# tick-ref-gps.net
KiCad netlist of a schematic drawn in EAGLE
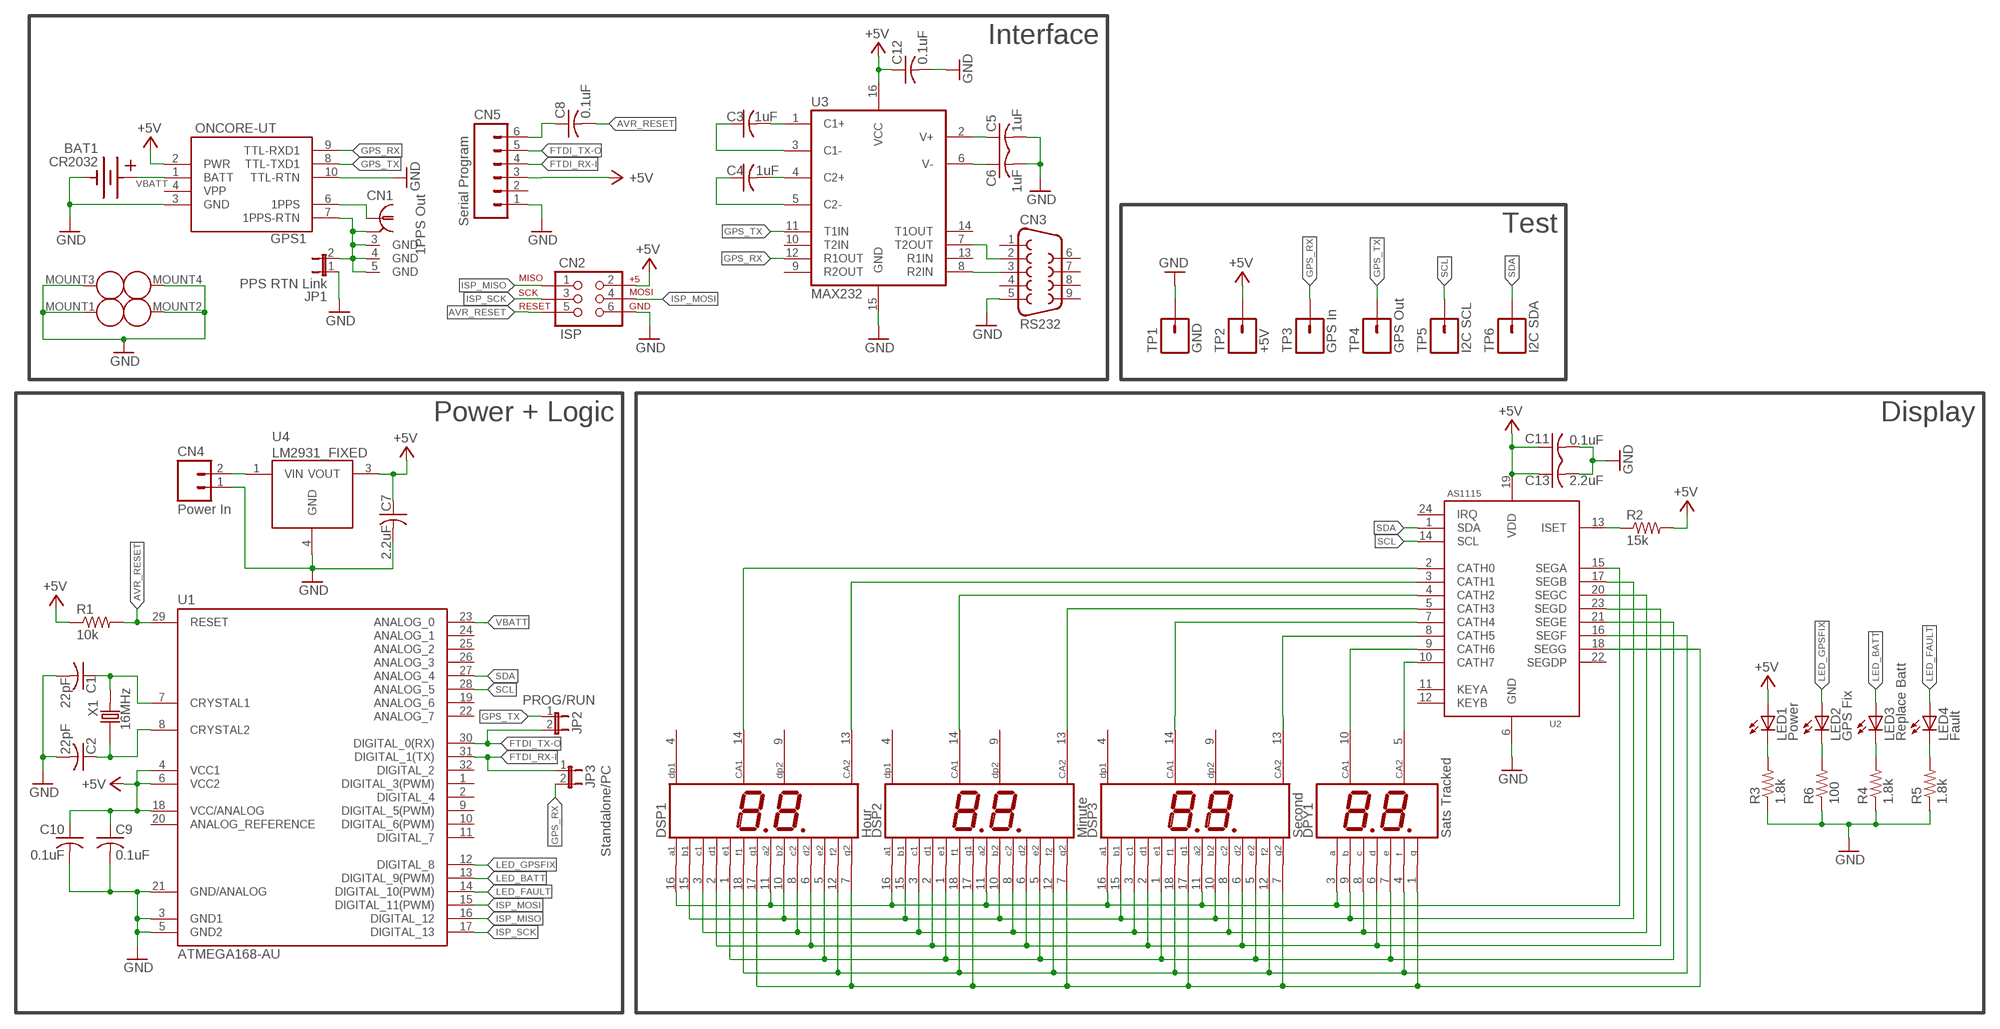
[diagram p0: schematic, sheet 1]

(export (version "E")
  (design (tool "Eeschema 10.0.6"))
  (components
    (comp (ref "BAT1")
      (value "CR2032")
      (footprint "eagle-import:BK-912-CR2032")
      (libsource (lib "eagle-import") (part "CR2032"))
    )
    (comp (ref "C1")
      (value "22pF")
      (footprint "eagle-import:C0603")
      (libsource (lib "eagle-import") (part "C-USC0603"))
    )
    (comp (ref "C2")
      (value "22pF")
      (footprint "eagle-import:C0603")
      (libsource (lib "eagle-import") (part "C-USC0603"))
    )
    (comp (ref "C3")
      (value "1uF")
      (footprint "eagle-import:C0603")
      (libsource (lib "eagle-import") (part "C-USC0603"))
    )
    (comp (ref "C4")
      (value "1uF")
      (footprint "eagle-import:C0603")
      (libsource (lib "eagle-import") (part "C-USC0603"))
    )
    (comp (ref "C5")
      (value "1uF")
      (footprint "eagle-import:C0603")
      (libsource (lib "eagle-import") (part "C-USC0603"))
    )
    (comp (ref "C6")
      (value "1uF")
      (footprint "eagle-import:C0603")
      (libsource (lib "eagle-import") (part "C-USC0603"))
    )
    (comp (ref "C7")
      (value "2.2uF")
      (footprint "eagle-import:C0805")
      (libsource (lib "eagle-import") (part "C-USC0805"))
    )
    (comp (ref "C8")
      (value "0.1uF")
      (footprint "eagle-import:C0603")
      (libsource (lib "eagle-import") (part "C-USC0603"))
    )
    (comp (ref "C9")
      (value "0.1uF")
      (footprint "eagle-import:C0603")
      (libsource (lib "eagle-import") (part "C-USC0603"))
    )
    (comp (ref "C10")
      (value "0.1uF")
      (footprint "eagle-import:C0603")
      (libsource (lib "eagle-import") (part "C-USC0603"))
    )
    (comp (ref "C11")
      (value "0.1uF")
      (footprint "eagle-import:C0603")
      (libsource (lib "eagle-import") (part "C-USC0603"))
    )
    (comp (ref "C12")
      (value "0.1uF")
      (footprint "eagle-import:C0603")
      (libsource (lib "eagle-import") (part "C-USC0603"))
    )
    (comp (ref "C13")
      (value "2.2uF")
      (footprint "eagle-import:C0805")
      (libsource (lib "eagle-import") (part "C-USC0805"))
    )
    (comp (ref "CN1")
      (value "1PPS Out")
      (footprint "eagle-import:B35N57")
      (libsource (lib "eagle-import") (part "B35N57"))
    )
    (comp (ref "CN2")
      (value "ISP")
      (footprint "eagle-import:2X3_LOCK")
      (libsource (lib "eagle-import") (part "AVR_SPI_PRG_62X3_LOCK"))
    )
    (comp (ref "CN3")
      (value "RS232")
      (footprint "eagle-import:F09VP")
      (libsource (lib "eagle-import") (part "F09VP"))
    )
    (comp (ref "CN4")
      (value "Power In")
      (footprint "eagle-import:MOLEX-1X2_LOCK")
      (libsource (lib "eagle-import") (part "M02POLAR_LOCK"))
    )
    (comp (ref "CN5")
      (value "Serial Program")
      (footprint "eagle-import:1X06_LOCK")
      (libsource (lib "eagle-import") (part "M06LOCK"))
    )
    (comp (ref "DPY1")
      (value "Sats Tracked")
      (footprint "eagle-import:LDD-F302NI")
      (libsource (lib "eagle-import") (part "LUMEX-LDD-F302NI"))
    )
    (comp (ref "DSP1")
      (value "Hour")
      (footprint "eagle-import:HDSP-R")
      (libsource (lib "eagle-import") (part "HD-K121"))
    )
    (comp (ref "DSP2")
      (value "Minute")
      (footprint "eagle-import:HDSP-R")
      (libsource (lib "eagle-import") (part "HD-K121"))
    )
    (comp (ref "DSP3")
      (value "Second")
      (footprint "eagle-import:HDSP-R")
      (libsource (lib "eagle-import") (part "HD-K121"))
    )
    (comp (ref "GPS1")
      (value "ONCORE-UT")
      (footprint "eagle-import:ONCORE-UT")
      (libsource (lib "eagle-import") (part "ONCORE-UT"))
    )
    (comp (ref "JP1")
      (value "PPS RTN Link")
      (footprint "eagle-import:SJ_2S-NO")
      (libsource (lib "eagle-import") (part "JUMPER-2SMD-NO"))
    )
    (comp (ref "JP2")
      (value "PROG/RUN")
      (footprint "eagle-import:1X02_LOCK")
      (libsource (lib "eagle-import") (part "JUMPER-2PTH_LOCK"))
    )
    (comp (ref "JP3")
      (value "Standalone/PC")
      (footprint "eagle-import:SJ_2S-NO")
      (libsource (lib "eagle-import") (part "JUMPER-2SMD-NO"))
    )
    (comp (ref "LED1")
      (value "Power")
      (footprint "eagle-import:LED5MM")
      (libsource (lib "eagle-import") (part "LED5MM"))
    )
    (comp (ref "LED2")
      (value "GPS Fix")
      (footprint "eagle-import:LED5MM")
      (libsource (lib "eagle-import") (part "LED5MM"))
    )
    (comp (ref "LED3")
      (value "Replace Batt")
      (footprint "eagle-import:LED5MM")
      (libsource (lib "eagle-import") (part "LED5MM"))
    )
    (comp (ref "LED4")
      (value "Fault")
      (footprint "eagle-import:LED5MM")
      (libsource (lib "eagle-import") (part "LED5MM"))
    )
    (comp (ref "R1")
      (value "10k")
      (footprint "eagle-import:R0603")
      (libsource (lib "eagle-import") (part "R-US_R0603"))
    )
    (comp (ref "R2")
      (value "15k")
      (footprint "eagle-import:R0603")
      (libsource (lib "eagle-import") (part "R-US_R0603"))
    )
    (comp (ref "R3")
      (value "1.8k")
      (footprint "eagle-import:R0603")
      (libsource (lib "eagle-import") (part "R-US_R0603"))
    )
    (comp (ref "R4")
      (value "1.8k")
      (footprint "eagle-import:R0603")
      (libsource (lib "eagle-import") (part "R-US_R0603"))
    )
    (comp (ref "R5")
      (value "1.8k")
      (footprint "eagle-import:R0603")
      (libsource (lib "eagle-import") (part "R-US_R0603"))
    )
    (comp (ref "R6")
      (value "100")
      (footprint "eagle-import:R0603")
      (libsource (lib "eagle-import") (part "R-US_R0603"))
    )
    (comp (ref "TP1")
      (value "GND")
      (footprint "eagle-import:1X01")
      (libsource (lib "eagle-import") (part "M01PTH"))
    )
    (comp (ref "TP2")
      (value "+5V")
      (footprint "eagle-import:1X01")
      (libsource (lib "eagle-import") (part "M01PTH"))
    )
    (comp (ref "TP3")
      (value "GPS In")
      (footprint "eagle-import:1X01")
      (libsource (lib "eagle-import") (part "M01PTH"))
    )
    (comp (ref "TP4")
      (value "GPS Out")
      (footprint "eagle-import:1X01")
      (libsource (lib "eagle-import") (part "M01PTH"))
    )
    (comp (ref "TP5")
      (value "I2C SCL")
      (footprint "eagle-import:1X01")
      (libsource (lib "eagle-import") (part "M01PTH"))
    )
    (comp (ref "TP6")
      (value "I2C SDA")
      (footprint "eagle-import:1X01")
      (libsource (lib "eagle-import") (part "M01PTH"))
    )
    (comp (ref "U1")
      (value "ATMEGA168-AU")
      (footprint "eagle-import:TQFP32-08")
      (libsource (lib "eagle-import") (part "ATMEGA168-AU"))
    )
    (comp (ref "U2")
      (value "AS1115")
      (footprint "eagle-import:QSOP24")
      (libsource (lib "eagle-import") (part "AS1115"))
    )
    (comp (ref "U3")
      (value "MAX232")
      (footprint "eagle-import:SO016")
      (libsource (lib "eagle-import") (part "MAX232SOIC16"))
    )
    (comp (ref "U4")
      (value "LM2931_FIXED")
      (footprint "eagle-import:DPAK")
      (libsource (lib "eagle-import") (part "LM2931_FIXED"))
    )
    (comp (ref "X1")
      (value "16MHz")
      (footprint "eagle-import:NX5032GA")
      (libsource (lib "eagle-import") (part "NX5032GA"))
    )
  )
  (nets
    (net (code "1") (name "+5V") (class "Default")
      (node (ref "C10") (pin "1") (pinfunction "1_1") (pintype "passive"))
      (node (ref "C11") (pin "1") (pinfunction "1_1") (pintype "passive"))
      (node (ref "C12") (pin "1") (pinfunction "1_1") (pintype "passive"))
      (node (ref "C13") (pin "1") (pinfunction "1_1") (pintype "passive"))
      (node (ref "C7") (pin "1") (pinfunction "1_1") (pintype "passive"))
      (node (ref "C9") (pin "1") (pinfunction "1_1") (pintype "passive"))
      (node (ref "CN2") (pin "2") (pinfunction "2_2") (pintype "passive"))
      (node (ref "CN5") (pin "3") (pinfunction "3_3") (pintype "passive"))
      (node (ref "GPS1") (pin "2") (pinfunction "PWR_2") (pintype "power_in"))
      (node (ref "LED1") (pin "A") (pinfunction "A_A") (pintype "passive"))
      (node (ref "R1") (pin "1") (pinfunction "1_1") (pintype "passive"))
      (node (ref "R2") (pin "2") (pinfunction "2_2") (pintype "passive"))
      (node (ref "TP2") (pin "1") (pinfunction "1_1") (pintype "passive"))
      (node (ref "U1") (pin "18") (pinfunction "VCC/ANALOG_18") (pintype "passive"))
      (node (ref "U1") (pin "4") (pinfunction "VCC1_4") (pintype "power_in"))
      (node (ref "U1") (pin "6") (pinfunction "VCC2_6") (pintype "power_in"))
      (node (ref "U2") (pin "19") (pinfunction "VDD_19") (pintype "power_in"))
      (node (ref "U3") (pin "16") (pinfunction "VCC_16") (pintype "bidirectional"))
      (node (ref "U4") (pin "3") (pinfunction "VOUT_3") (pintype "bidirectional"))
    )
    (net (code "2") (name "/VPP") (class "Default")
      (node (ref "GPS1") (pin "4") (pinfunction "VPP_4") (pintype "power_in"))
    )
    (net (code "3") (name "AVR_RESET") (class "Default")
      (node (ref "C8") (pin "2") (pinfunction "2_2") (pintype "passive"))
      (node (ref "CN2") (pin "5") (pinfunction "5_5") (pintype "passive"))
      (node (ref "R1") (pin "2") (pinfunction "2_2") (pintype "passive"))
      (node (ref "U1") (pin "29") (pinfunction "RESET_29") (pintype "bidirectional"))
    )
    (net (code "4") (name "FTDI_RX-I") (class "Default")
      (node (ref "CN5") (pin "4") (pinfunction "4_4") (pintype "passive"))
      (node (ref "JP3") (pin "1") (pinfunction "1_1") (pintype "passive"))
      (node (ref "U1") (pin "31") (pinfunction "DIGITAL_1(TX)_31") (pintype "bidirectional"))
    )
    (net (code "5") (name "FTDI_TX-O") (class "Default")
      (node (ref "CN5") (pin "5") (pinfunction "5_5") (pintype "passive"))
      (node (ref "JP2") (pin "2") (pinfunction "2_2") (pintype "passive"))
      (node (ref "U1") (pin "30") (pinfunction "DIGITAL_0(RX)_30") (pintype "bidirectional"))
    )
    (net (code "6") (name "GND") (class "Default")
      (node (ref "BAT1") (pin "-") (pinfunction "-1_-") (pintype "power_in"))
      (node (ref "C1") (pin "2") (pinfunction "2_2") (pintype "passive"))
      (node (ref "C10") (pin "2") (pinfunction "2_2") (pintype "passive"))
      (node (ref "C11") (pin "2") (pinfunction "2_2") (pintype "passive"))
      (node (ref "C12") (pin "2") (pinfunction "2_2") (pintype "passive"))
      (node (ref "C13") (pin "2") (pinfunction "2_2") (pintype "passive"))
      (node (ref "C2") (pin "2") (pinfunction "2_2") (pintype "passive"))
      (node (ref "C5") (pin "2") (pinfunction "2_2") (pintype "passive"))
      (node (ref "C6") (pin "2") (pinfunction "2_2") (pintype "passive"))
      (node (ref "C7") (pin "2") (pinfunction "2_2") (pintype "passive"))
      (node (ref "C9") (pin "2") (pinfunction "2_2") (pintype "passive"))
      (node (ref "CN2") (pin "6") (pinfunction "6_6") (pintype "passive"))
      (node (ref "CN3") (pin "5") (pinfunction "5_5") (pintype "passive"))
      (node (ref "CN4") (pin "1") (pinfunction "1_1") (pintype "passive"))
      (node (ref "CN5") (pin "1") (pinfunction "1_1") (pintype "passive"))
      (node (ref "GPS1") (pin "10") (pinfunction "TTL-RTN_10") (pintype "power_in"))
      (node (ref "GPS1") (pin "3") (pinfunction "GND_3") (pintype "power_in"))
      (node (ref "GPS1") (pin "MOUNT1") (pinfunction "MOUNTHOLE1_MOUNT1") (pintype "passive"))
      (node (ref "GPS1") (pin "MOUNT2") (pinfunction "MOUNTHOLE2_MOUNT2") (pintype "passive"))
      (node (ref "GPS1") (pin "MOUNT3") (pinfunction "MOUNTHOLE3_MOUNT3") (pintype "passive"))
      (node (ref "GPS1") (pin "MOUNT4") (pinfunction "MOUNTHOLE4_MOUNT4") (pintype "passive"))
      (node (ref "JP1") (pin "1") (pinfunction "1_1") (pintype "passive"))
      (node (ref "R3") (pin "1") (pinfunction "1_1") (pintype "passive"))
      (node (ref "R4") (pin "1") (pinfunction "1_1") (pintype "passive"))
      (node (ref "R5") (pin "1") (pinfunction "1_1") (pintype "passive"))
      (node (ref "R6") (pin "1") (pinfunction "1_1") (pintype "passive"))
      (node (ref "TP1") (pin "1") (pinfunction "1_1") (pintype "passive"))
      (node (ref "U1") (pin "21") (pinfunction "GND/ANALOG_21") (pintype "power_in"))
      (node (ref "U1") (pin "3") (pinfunction "GND1_3") (pintype "power_in"))
      (node (ref "U1") (pin "5") (pinfunction "GND2_5") (pintype "power_in"))
      (node (ref "U2") (pin "6") (pinfunction "GND_6") (pintype "power_in"))
      (node (ref "U3") (pin "15") (pinfunction "GND_15") (pintype "bidirectional"))
      (node (ref "U4") (pin "4") (pinfunction "GND_4") (pintype "bidirectional"))
    )
    (net (code "7") (name "GPS_RX") (class "Default")
      (node (ref "GPS1") (pin "9") (pinfunction "TTL-RXD1_9") (pintype "input"))
      (node (ref "JP3") (pin "2") (pinfunction "2_2") (pintype "passive"))
      (node (ref "TP3") (pin "1") (pinfunction "1_1") (pintype "passive"))
      (node (ref "U3") (pin "12") (pinfunction "R1OUT_12") (pintype "output"))
    )
    (net (code "8") (name "GPS_TX") (class "Default")
      (node (ref "GPS1") (pin "8") (pinfunction "TTL-TXD1_8") (pintype "output"))
      (node (ref "JP2") (pin "1") (pinfunction "1_1") (pintype "passive"))
      (node (ref "TP4") (pin "1") (pinfunction "1_1") (pintype "passive"))
      (node (ref "U3") (pin "11") (pinfunction "T1IN_11") (pintype "input"))
    )
    (net (code "9") (name "ISP_MISO") (class "Default")
      (node (ref "CN2") (pin "1") (pinfunction "1_1") (pintype "passive"))
      (node (ref "U1") (pin "16") (pinfunction "DIGITAL_12_16") (pintype "bidirectional"))
    )
    (net (code "10") (name "ISP_MOSI") (class "Default")
      (node (ref "CN2") (pin "4") (pinfunction "4_4") (pintype "passive"))
      (node (ref "U1") (pin "15") (pinfunction "DIGITAL_11(PWM)_15") (pintype "bidirectional"))
    )
    (net (code "11") (name "ISP_SCK") (class "Default")
      (node (ref "CN2") (pin "3") (pinfunction "3_3") (pintype "passive"))
      (node (ref "U1") (pin "17") (pinfunction "DIGITAL_13_17") (pintype "bidirectional"))
    )
    (net (code "12") (name "LED_BATT") (class "Default")
      (node (ref "LED3") (pin "A") (pinfunction "A_A") (pintype "passive"))
      (node (ref "U1") (pin "13") (pinfunction "DIGITAL_9(PWM)_13") (pintype "bidirectional"))
    )
    (net (code "13") (name "LED_FAULT") (class "Default")
      (node (ref "LED4") (pin "A") (pinfunction "A_A") (pintype "passive"))
      (node (ref "U1") (pin "14") (pinfunction "DIGITAL_10(PWM)_14") (pintype "bidirectional"))
    )
    (net (code "14") (name "LED_GPSFIX") (class "Default")
      (node (ref "LED2") (pin "A") (pinfunction "A_A") (pintype "passive"))
      (node (ref "U1") (pin "12") (pinfunction "DIGITAL_8_12") (pintype "bidirectional"))
    )
    (net (code "15") (name "Net-(C8-Pad1)") (class "Default")
      (node (ref "C8") (pin "1") (pinfunction "1_1") (pintype "passive"))
      (node (ref "CN5") (pin "6") (pinfunction "6_6") (pintype "passive"))
    )
    (net (code "16") (name "Net-(CN1A-GND)") (class "Default")
      (node (ref "CN1") (pin "2") (pinfunction "GND_2") (pintype "power_in"))
      (node (ref "CN1") (pin "3") (pinfunction "GND_3") (pintype "power_in"))
      (node (ref "CN1") (pin "4") (pinfunction "GND_4") (pintype "power_in"))
      (node (ref "CN1") (pin "5") (pinfunction "GND_5") (pintype "power_in"))
      (node (ref "GPS1") (pin "7") (pinfunction "1PPS-RTN_7") (pintype "power_in"))
      (node (ref "JP1") (pin "2") (pinfunction "2_2") (pintype "passive"))
    )
    (net (code "17") (name "Net-(DPY1-A)") (class "Default")
      (node (ref "DPY1") (pin "3") (pinfunction "A_3") (pintype "passive"))
      (node (ref "DSP1") (pin "11") (pinfunction "A2_11") (pintype "passive"))
      (node (ref "DSP1") (pin "16") (pinfunction "A1_16") (pintype "passive"))
      (node (ref "DSP2") (pin "11") (pinfunction "A2_11") (pintype "passive"))
      (node (ref "DSP2") (pin "16") (pinfunction "A1_16") (pintype "passive"))
      (node (ref "DSP3") (pin "11") (pinfunction "A2_11") (pintype "passive"))
      (node (ref "DSP3") (pin "16") (pinfunction "A1_16") (pintype "passive"))
      (node (ref "U2") (pin "15") (pinfunction "SEGA_15") (pintype "output"))
    )
    (net (code "18") (name "Net-(DPY1-B)") (class "Default")
      (node (ref "DPY1") (pin "9") (pinfunction "B_9") (pintype "passive"))
      (node (ref "DSP1") (pin "10") (pinfunction "B2_10") (pintype "passive"))
      (node (ref "DSP1") (pin "15") (pinfunction "B1_15") (pintype "passive"))
      (node (ref "DSP2") (pin "10") (pinfunction "B2_10") (pintype "passive"))
      (node (ref "DSP2") (pin "15") (pinfunction "B1_15") (pintype "passive"))
      (node (ref "DSP3") (pin "10") (pinfunction "B2_10") (pintype "passive"))
      (node (ref "DSP3") (pin "15") (pinfunction "B1_15") (pintype "passive"))
      (node (ref "U2") (pin "17") (pinfunction "SEGB_17") (pintype "output"))
    )
    (net (code "19") (name "Net-(DPY1-C)") (class "Default")
      (node (ref "DPY1") (pin "8") (pinfunction "C_8") (pintype "passive"))
      (node (ref "DSP1") (pin "3") (pinfunction "C1_3") (pintype "passive"))
      (node (ref "DSP1") (pin "8") (pinfunction "C2_8") (pintype "passive"))
      (node (ref "DSP2") (pin "3") (pinfunction "C1_3") (pintype "passive"))
      (node (ref "DSP2") (pin "8") (pinfunction "C2_8") (pintype "passive"))
      (node (ref "DSP3") (pin "3") (pinfunction "C1_3") (pintype "passive"))
      (node (ref "DSP3") (pin "8") (pinfunction "C2_8") (pintype "passive"))
      (node (ref "U2") (pin "20") (pinfunction "SEGC_20") (pintype "output"))
    )
    (net (code "20") (name "Net-(DPY1-CA1)") (class "Default")
      (node (ref "DPY1") (pin "10") (pinfunction "CA1_10") (pintype "passive"))
      (node (ref "U2") (pin "9") (pinfunction "CATH6_9") (pintype "output"))
    )
    (net (code "21") (name "Net-(DPY1-CA2)") (class "Default")
      (node (ref "DPY1") (pin "5") (pinfunction "CA2_5") (pintype "passive"))
      (node (ref "U2") (pin "10") (pinfunction "CATH7_10") (pintype "output"))
    )
    (net (code "22") (name "Net-(DPY1-D)") (class "Default")
      (node (ref "DPY1") (pin "6") (pinfunction "D_6") (pintype "passive"))
      (node (ref "DSP1") (pin "2") (pinfunction "D1_2") (pintype "passive"))
      (node (ref "DSP1") (pin "6") (pinfunction "D2_6") (pintype "passive"))
      (node (ref "DSP2") (pin "2") (pinfunction "D1_2") (pintype "passive"))
      (node (ref "DSP2") (pin "6") (pinfunction "D2_6") (pintype "passive"))
      (node (ref "DSP3") (pin "2") (pinfunction "D1_2") (pintype "passive"))
      (node (ref "DSP3") (pin "6") (pinfunction "D2_6") (pintype "passive"))
      (node (ref "U2") (pin "23") (pinfunction "SEGD_23") (pintype "output"))
    )
    (net (code "23") (name "Net-(DPY1-E)") (class "Default")
      (node (ref "DPY1") (pin "7") (pinfunction "E_7") (pintype "passive"))
      (node (ref "DSP1") (pin "1") (pinfunction "E1_1") (pintype "passive"))
      (node (ref "DSP1") (pin "5") (pinfunction "E2_5") (pintype "passive"))
      (node (ref "DSP2") (pin "1") (pinfunction "E1_1") (pintype "passive"))
      (node (ref "DSP2") (pin "5") (pinfunction "E2_5") (pintype "passive"))
      (node (ref "DSP3") (pin "1") (pinfunction "E1_1") (pintype "passive"))
      (node (ref "DSP3") (pin "5") (pinfunction "E2_5") (pintype "passive"))
      (node (ref "U2") (pin "21") (pinfunction "SEGE_21") (pintype "output"))
    )
    (net (code "24") (name "Net-(DPY1-F)") (class "Default")
      (node (ref "DPY1") (pin "4") (pinfunction "F_4") (pintype "passive"))
      (node (ref "DSP1") (pin "12") (pinfunction "F2_12") (pintype "passive"))
      (node (ref "DSP1") (pin "18") (pinfunction "F1_18") (pintype "passive"))
      (node (ref "DSP2") (pin "12") (pinfunction "F2_12") (pintype "passive"))
      (node (ref "DSP2") (pin "18") (pinfunction "F1_18") (pintype "passive"))
      (node (ref "DSP3") (pin "12") (pinfunction "F2_12") (pintype "passive"))
      (node (ref "DSP3") (pin "18") (pinfunction "F1_18") (pintype "passive"))
      (node (ref "U2") (pin "16") (pinfunction "SEGF_16") (pintype "output"))
    )
    (net (code "25") (name "Net-(DPY1-G)") (class "Default")
      (node (ref "DPY1") (pin "1") (pinfunction "G_1") (pintype "passive"))
      (node (ref "DSP1") (pin "17") (pinfunction "G1_17") (pintype "passive"))
      (node (ref "DSP1") (pin "7") (pinfunction "G2_7") (pintype "passive"))
      (node (ref "DSP2") (pin "17") (pinfunction "G1_17") (pintype "passive"))
      (node (ref "DSP2") (pin "7") (pinfunction "G2_7") (pintype "passive"))
      (node (ref "DSP3") (pin "17") (pinfunction "G1_17") (pintype "passive"))
      (node (ref "DSP3") (pin "7") (pinfunction "G2_7") (pintype "passive"))
      (node (ref "U2") (pin "18") (pinfunction "SEGG_18") (pintype "output"))
    )
    (net (code "26") (name "Net-(DSP1-CA1)") (class "Default")
      (node (ref "DSP1") (pin "14") (pinfunction "CA1_14") (pintype "passive"))
      (node (ref "U2") (pin "2") (pinfunction "CATH0_2") (pintype "output"))
    )
    (net (code "27") (name "Net-(DSP1-CA2)") (class "Default")
      (node (ref "DSP1") (pin "13") (pinfunction "CA2_13") (pintype "passive"))
      (node (ref "U2") (pin "3") (pinfunction "CATH1_3") (pintype "output"))
    )
    (net (code "28") (name "Net-(DSP2-CA1)") (class "Default")
      (node (ref "DSP2") (pin "14") (pinfunction "CA1_14") (pintype "passive"))
      (node (ref "U2") (pin "4") (pinfunction "CATH2_4") (pintype "output"))
    )
    (net (code "29") (name "Net-(DSP2-CA2)") (class "Default")
      (node (ref "DSP2") (pin "13") (pinfunction "CA2_13") (pintype "passive"))
      (node (ref "U2") (pin "5") (pinfunction "CATH3_5") (pintype "output"))
    )
    (net (code "30") (name "Net-(DSP3-CA1)") (class "Default")
      (node (ref "DSP3") (pin "14") (pinfunction "CA1_14") (pintype "passive"))
      (node (ref "U2") (pin "7") (pinfunction "CATH4_7") (pintype "output"))
    )
    (net (code "31") (name "Net-(DSP3-CA2)") (class "Default")
      (node (ref "DSP3") (pin "13") (pinfunction "CA2_13") (pintype "passive"))
      (node (ref "U2") (pin "8") (pinfunction "CATH5_8") (pintype "output"))
    )
    (net (code "32") (name "Net-(GPS1A-1PPS)") (class "Default")
      (node (ref "CN1") (pin "1") (pinfunction "1_1") (pintype "passive"))
      (node (ref "GPS1") (pin "6") (pinfunction "1PPS_6") (pintype "output"))
    )
    (net (code "33") (name "Net-(LED1-C)") (class "Default")
      (node (ref "LED1") (pin "K") (pinfunction "C_K") (pintype "passive"))
      (node (ref "R3") (pin "2") (pinfunction "2_2") (pintype "passive"))
    )
    (net (code "34") (name "Net-(LED2-C)") (class "Default")
      (node (ref "LED2") (pin "K") (pinfunction "C_K") (pintype "passive"))
      (node (ref "R6") (pin "2") (pinfunction "2_2") (pintype "passive"))
    )
    (net (code "35") (name "Net-(LED3-C)") (class "Default")
      (node (ref "LED3") (pin "K") (pinfunction "C_K") (pintype "passive"))
      (node (ref "R4") (pin "2") (pinfunction "2_2") (pintype "passive"))
    )
    (net (code "36") (name "Net-(LED4-C)") (class "Default")
      (node (ref "LED4") (pin "K") (pinfunction "C_K") (pintype "passive"))
      (node (ref "R5") (pin "2") (pinfunction "2_2") (pintype "passive"))
    )
    (net (code "37") (name "Net-(U1-CRYSTAL1)") (class "Default")
      (node (ref "C1") (pin "1") (pinfunction "1_1") (pintype "passive"))
      (node (ref "U1") (pin "7") (pinfunction "CRYSTAL1_7") (pintype "bidirectional"))
      (node (ref "X1") (pin "P$2") (pinfunction "2_P$2") (pintype "passive"))
    )
    (net (code "38") (name "Net-(U1-CRYSTAL2)") (class "Default")
      (node (ref "C2") (pin "1") (pinfunction "1_1") (pintype "passive"))
      (node (ref "U1") (pin "8") (pinfunction "CRYSTAL2_8") (pintype "bidirectional"))
      (node (ref "X1") (pin "P$1") (pinfunction "1_P$1") (pintype "passive"))
    )
    (net (code "39") (name "Net-(U2-ISET)") (class "Default")
      (node (ref "R2") (pin "1") (pinfunction "1_1") (pintype "passive"))
      (node (ref "U2") (pin "13") (pinfunction "ISET_13") (pintype "input"))
    )
    (net (code "40") (name "Net-(U3-C1+)") (class "Default")
      (node (ref "C3") (pin "2") (pinfunction "2_2") (pintype "passive"))
      (node (ref "U3") (pin "1") (pinfunction "C1+_1") (pintype "bidirectional"))
    )
    (net (code "41") (name "Net-(U3-C1-)") (class "Default")
      (node (ref "C3") (pin "1") (pinfunction "1_1") (pintype "passive"))
      (node (ref "U3") (pin "3") (pinfunction "C1-_3") (pintype "bidirectional"))
    )
    (net (code "42") (name "Net-(U3-C2+)") (class "Default")
      (node (ref "C4") (pin "2") (pinfunction "2_2") (pintype "passive"))
      (node (ref "U3") (pin "4") (pinfunction "C2+_4") (pintype "bidirectional"))
    )
    (net (code "43") (name "Net-(U3-C2-)") (class "Default")
      (node (ref "C4") (pin "1") (pinfunction "1_1") (pintype "passive"))
      (node (ref "U3") (pin "5") (pinfunction "C2-_5") (pintype "bidirectional"))
    )
    (net (code "44") (name "Net-(U3-R2IN)") (class "Default")
      (node (ref "CN3") (pin "3") (pinfunction "3_3") (pintype "passive"))
      (node (ref "U3") (pin "8") (pinfunction "R2IN_8") (pintype "input"))
    )
    (net (code "45") (name "Net-(U3-T2OUT)") (class "Default")
      (node (ref "CN3") (pin "2") (pinfunction "2_2") (pintype "passive"))
      (node (ref "U3") (pin "7") (pinfunction "T2OUT_7") (pintype "output"))
    )
    (net (code "46") (name "Net-(U3-V+)") (class "Default")
      (node (ref "C5") (pin "1") (pinfunction "1_1") (pintype "passive"))
      (node (ref "U3") (pin "2") (pinfunction "V+_2") (pintype "bidirectional"))
    )
    (net (code "47") (name "Net-(U3-V-)") (class "Default")
      (node (ref "C6") (pin "1") (pinfunction "1_1") (pintype "passive"))
      (node (ref "U3") (pin "6") (pinfunction "V-_6") (pintype "bidirectional"))
    )
    (net (code "48") (name "Net-(U4-VIN)") (class "Default")
      (node (ref "CN4") (pin "2") (pinfunction "2_2") (pintype "passive"))
      (node (ref "U4") (pin "1") (pinfunction "VIN_1") (pintype "bidirectional"))
    )
    (net (code "49") (name "SCL") (class "Default")
      (node (ref "TP5") (pin "1") (pinfunction "1_1") (pintype "passive"))
      (node (ref "U1") (pin "28") (pinfunction "ANALOG_5_28") (pintype "bidirectional"))
      (node (ref "U2") (pin "14") (pinfunction "SCL_14") (pintype "bidirectional"))
    )
    (net (code "50") (name "SDA") (class "Default")
      (node (ref "TP6") (pin "1") (pinfunction "1_1") (pintype "passive"))
      (node (ref "U1") (pin "27") (pinfunction "ANALOG_4_27") (pintype "bidirectional"))
      (node (ref "U2") (pin "1") (pinfunction "SDA_1") (pintype "bidirectional"))
    )
    (net (code "51") (name "VBATT") (class "Default")
      (node (ref "BAT1") (pin "+1") (pinfunction "+2_+1") (pintype "power_in"))
      (node (ref "GPS1") (pin "1") (pinfunction "BATT_1") (pintype "power_in"))
      (node (ref "U1") (pin "23") (pinfunction "ANALOG_0_23") (pintype "bidirectional"))
    )
    (net (code "52") (name "unconnected-(CN3-Pad1)") (class "Default")
      (node (ref "CN3") (pin "1") (pinfunction "1_1") (pintype "passive"))
    )
    (net (code "53") (name "unconnected-(CN3-Pad4)") (class "Default")
      (node (ref "CN3") (pin "4") (pinfunction "4_4") (pintype "passive"))
    )
    (net (code "54") (name "unconnected-(CN3-Pad6)") (class "Default")
      (node (ref "CN3") (pin "6") (pinfunction "6_6") (pintype "passive"))
    )
    (net (code "55") (name "unconnected-(CN3-Pad7)") (class "Default")
      (node (ref "CN3") (pin "7") (pinfunction "7_7") (pintype "passive"))
    )
    (net (code "56") (name "unconnected-(CN3-Pad8)") (class "Default")
      (node (ref "CN3") (pin "8") (pinfunction "8_8") (pintype "passive"))
    )
    (net (code "57") (name "unconnected-(CN3-Pad9)") (class "Default")
      (node (ref "CN3") (pin "9") (pinfunction "9_9") (pintype "passive"))
    )
    (net (code "58") (name "unconnected-(CN5-Pad2)") (class "Default")
      (node (ref "CN5") (pin "2") (pinfunction "2_2") (pintype "passive"))
    )
    (net (code "59") (name "unconnected-(DSP1-DP1-Pad4)") (class "Default")
      (node (ref "DSP1") (pin "4") (pinfunction "DP1_4") (pintype "passive"))
    )
    (net (code "60") (name "unconnected-(DSP1-DP2-Pad9)") (class "Default")
      (node (ref "DSP1") (pin "9") (pinfunction "DP2_9") (pintype "passive"))
    )
    (net (code "61") (name "unconnected-(DSP2-DP1-Pad4)") (class "Default")
      (node (ref "DSP2") (pin "4") (pinfunction "DP1_4") (pintype "passive"))
    )
    (net (code "62") (name "unconnected-(DSP2-DP2-Pad9)") (class "Default")
      (node (ref "DSP2") (pin "9") (pinfunction "DP2_9") (pintype "passive"))
    )
    (net (code "63") (name "unconnected-(DSP3-DP1-Pad4)") (class "Default")
      (node (ref "DSP3") (pin "4") (pinfunction "DP1_4") (pintype "passive"))
    )
    (net (code "64") (name "unconnected-(DSP3-DP2-Pad9)") (class "Default")
      (node (ref "DSP3") (pin "9") (pinfunction "DP2_9") (pintype "passive"))
    )
    (net (code "65") (name "unconnected-(U1-ANALOG_1-Pad24)") (class "Default")
      (node (ref "U1") (pin "24") (pinfunction "ANALOG_1_24") (pintype "bidirectional"))
    )
    (net (code "66") (name "unconnected-(U1-ANALOG_2-Pad25)") (class "Default")
      (node (ref "U1") (pin "25") (pinfunction "ANALOG_2_25") (pintype "bidirectional"))
    )
    (net (code "67") (name "unconnected-(U1-ANALOG_3-Pad26)") (class "Default")
      (node (ref "U1") (pin "26") (pinfunction "ANALOG_3_26") (pintype "bidirectional"))
    )
    (net (code "68") (name "unconnected-(U1-ANALOG_6-Pad19)") (class "Default")
      (node (ref "U1") (pin "19") (pinfunction "ANALOG_6_19") (pintype "passive"))
    )
    (net (code "69") (name "unconnected-(U1-ANALOG_7-Pad22)") (class "Default")
      (node (ref "U1") (pin "22") (pinfunction "ANALOG_7_22") (pintype "passive"))
    )
    (net (code "70") (name "unconnected-(U1-ANALOG_REFERENCE-Pad20)") (class "Default")
      (node (ref "U1") (pin "20") (pinfunction "ANALOG_REFERENCE_20") (pintype "passive"))
    )
    (net (code "71") (name "unconnected-(U1-DIGITAL_2-Pad32)") (class "Default")
      (node (ref "U1") (pin "32") (pinfunction "DIGITAL_2_32") (pintype "bidirectional"))
    )
    (net (code "72") (name "unconnected-(U1-DIGITAL_3(PWM)-Pad1)") (class "Default")
      (node (ref "U1") (pin "1") (pinfunction "DIGITAL_3(PWM)_1") (pintype "bidirectional"))
    )
    (net (code "73") (name "unconnected-(U1-DIGITAL_4-Pad2)") (class "Default")
      (node (ref "U1") (pin "2") (pinfunction "DIGITAL_4_2") (pintype "bidirectional"))
    )
    (net (code "74") (name "unconnected-(U1-DIGITAL_5(PWM)-Pad9)") (class "Default")
      (node (ref "U1") (pin "9") (pinfunction "DIGITAL_5(PWM)_9") (pintype "bidirectional"))
    )
    (net (code "75") (name "unconnected-(U1-DIGITAL_6(PWM)-Pad10)") (class "Default")
      (node (ref "U1") (pin "10") (pinfunction "DIGITAL_6(PWM)_10") (pintype "bidirectional"))
    )
    (net (code "76") (name "unconnected-(U1-DIGITAL_7-Pad11)") (class "Default")
      (node (ref "U1") (pin "11") (pinfunction "DIGITAL_7_11") (pintype "bidirectional"))
    )
    (net (code "77") (name "unconnected-(U2-IRQ-Pad24)") (class "Default")
      (node (ref "U2") (pin "24") (pinfunction "IRQ_24") (pintype "output"))
    )
    (net (code "78") (name "unconnected-(U2-KEYA-Pad11)") (class "Default")
      (node (ref "U2") (pin "11") (pinfunction "KEYA_11") (pintype "bidirectional"))
    )
    (net (code "79") (name "unconnected-(U2-KEYB-Pad12)") (class "Default")
      (node (ref "U2") (pin "12") (pinfunction "KEYB_12") (pintype "bidirectional"))
    )
    (net (code "80") (name "unconnected-(U2-SEGDP-Pad22)") (class "Default")
      (node (ref "U2") (pin "22") (pinfunction "SEGDP_22") (pintype "output"))
    )
    (net (code "81") (name "unconnected-(U3-R1IN-Pad13)") (class "Default")
      (node (ref "U3") (pin "13") (pinfunction "R1IN_13") (pintype "input"))
    )
    (net (code "82") (name "unconnected-(U3-R2OUT-Pad9)") (class "Default")
      (node (ref "U3") (pin "9") (pinfunction "R2OUT_9") (pintype "output"))
    )
    (net (code "83") (name "unconnected-(U3-T1OUT-Pad14)") (class "Default")
      (node (ref "U3") (pin "14") (pinfunction "T1OUT_14") (pintype "output"))
    )
    (net (code "84") (name "unconnected-(U3-T2IN-Pad10)") (class "Default")
      (node (ref "U3") (pin "10") (pinfunction "T2IN_10") (pintype "input"))
    )
  )
)
